# MCU.net
KiCad netlist of a schematic drawn in Altium Designer
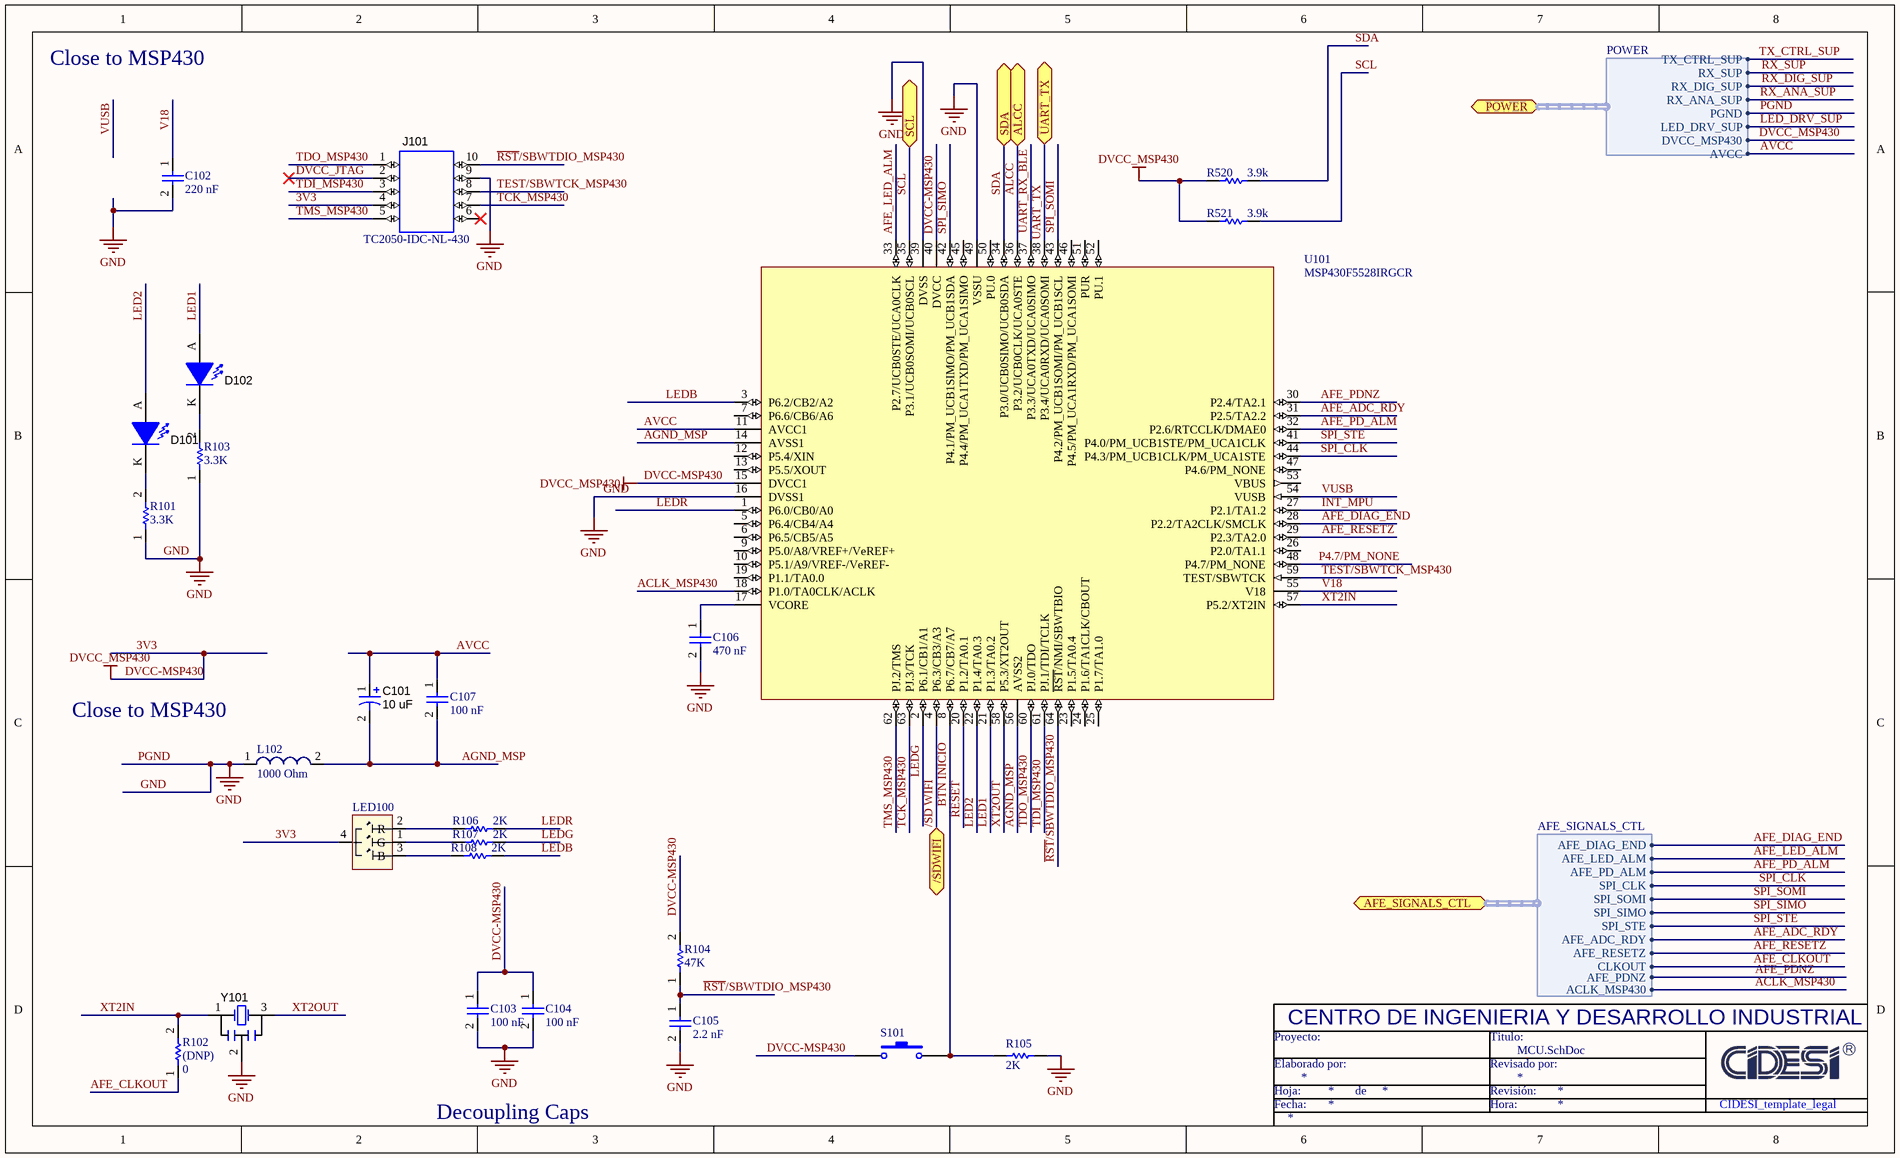
[diagram p0: MCU.SchDoc]

(export (version "E")
  (design (tool "Eeschema 10.0.6"))
  (components
    (comp (ref "C101")
      (value "10 uF")
      (footprint "C0603_P")
      (description "NICHICON - F981A106MMA - CAPACITOR TANT, 10UF, 10V 20%")
      (libsource (lib "TarjetaPrincipalV1_4") (part "F981A106MMA"))
    )
    (comp (ref "C102")
      (value "220 nF")
      (footprint "C0402")
      (description "TDK - C1005X7R1C224K050BC - CAP CERAMIC, 0.22UF, 16V, X7R, 0402")
      (libsource (lib "TarjetaPrincipalV1_4") (part "C1005X7R1C224K050BC"))
    )
    (comp (ref "C103")
      (value "100 nF")
      (footprint "C0402")
      (description "TDK - C1005X7R1H104M050BB - CAP CERAMIC, 0.1UF, 50V, X7R, 0402")
      (libsource (lib "TarjetaPrincipalV1_4") (part "C1005X7R1H104M050BB"))
    )
    (comp (ref "C104")
      (value "100 nF")
      (footprint "C0402")
      (description "TDK - C1005X7R1H104M050BB - CAP CERAMIC, 0.1UF, 50V, X7R, 0402")
      (libsource (lib "TarjetaPrincipalV1_4") (part "C1005X7R1H104M050BB"))
    )
    (comp (ref "C105")
      (value "2.2 nF")
      (footprint "C0402")
      (description "TDK - C1005X7R1H222K050BA - CAPACITOR CERAMIC 2200PF, 50V, X7R, 10%, 0402")
      (libsource (lib "5551-D_Wrist Watch") (part "C1005X7R1H222K050BA"))
    )
    (comp (ref "C106")
      (value "470 nF")
      (footprint "C0402")
      (description "TDK - C1005X5R1E474K050BB - CAP CERAMIC, 0.47UF, 25V, X5R, 0402")
      (libsource (lib "TarjetaPrincipalV1_4") (part "C1005X5R1E474K050BB"))
    )
    (comp (ref "C107")
      (value "100 nF")
      (footprint "C0402")
      (description "TDK - C1005X7R1H104M050BB - CAP CERAMIC, 0.1UF, 50V, X7R, 0402")
      (libsource (lib "TarjetaPrincipalV1_4") (part "C1005X7R1H104M050BB"))
    )
    (comp (ref "D101")
      (value "KPHHS-1005QBC-D-V")
      (footprint "LED_0402_BLUE")
      (description "KINGBRIGHT - KPHHS-1005QBC-D-V - LED, 0402, BLUE")
      (libsource (lib "TarjetaPrincipalV1_4") (part "LNJ947W8CRA"))
    )
    (comp (ref "D102")
      (value "2290341")
      (footprint "LED_0402_GREEN")
      (description "KINGBRIGHT - KPHHS-1005MGCK - LED, 0402, GREEN")
      (libsource (lib "TarjetaPrincipalV1_4") (part "APHHS1005CGCK"))
    )
    (comp (ref "J101")
      (value "TC2050-IDC-NL-430")
      (footprint "TC2050-IDC-NL")
      (description "CONNECTOR, PLUG OF NAILS CABLE, DUAL ROW, VERTICAL, 10-PIN")
      (fields (field (name "MANUFACTURER") "TAG CONNECT"))
      (libsource (lib "TarjetaPrincipalV1_4") (part "TC2050-IDC-NL-430"))
    )
    (comp (ref "L102")
      (value "1000 Ohm")
      (footprint "SMD 0402")
      (description "SMD EMI Suppression Ferrite Beads WE-CBF HF, Z= 1000 Ohm")
      (fields
        (field (name "PARTNO") "742841210")
        (field (name "MANUFACTURER") "Würth Elektronik eiSos GmbH")
        (field (name "CREATED BY") "Christin Zierenner")
      )
      (libsource (lib "TarjetaPrincipalV1_4") (part "WE-CBF HF 0402, 742841210"))
    )
    (comp (ref "LED100")
      (value "LED RGB AnodoComun")
      (footprint "LED-RGB 0606")
      (libsource (lib "TarjetaPrincipalV1_4") (part "LED RGB AnodoComun"))
    )
    (comp (ref "R101")
      (value "3.3K")
      (footprint "0201")
      (description "VISHAY DALE - CRCW02013K30FNED - RESISTOR, THICK FILM, 3.3 KOHM, 50 mW, 1%, FULL REEL")
      (libsource (lib "TarjetaPrincipalV1_4") (part "CRCW02013K30FNED"))
    )
    (comp (ref "R102")
      (value "(DNP)")
      (footprint "0201")
      (description "VISHAY DALE - CRCW02010000Z0ED - RESISTOR, CHIP, JUMPER, ZERO OHM, 50mW, FULL REEL")
      (fields (field (name "ALTIUM_VALUE") "0"))
      (libsource (lib "TarjetaPrincipalV1_4") (part "CRCW02010000Z0ED"))
    )
    (comp (ref "R103")
      (value "3.3K")
      (footprint "0201")
      (description "VISHAY DALE - CRCW02013K30FNED - RESISTOR, THICK FILM, 3.3 KOHM, 50 mW, 1%, FULL REEL")
      (libsource (lib "TarjetaPrincipalV1_4") (part "CRCW02013K30FNED"))
    )
    (comp (ref "R104")
      (value "47K")
      (footprint "0201")
      (description "VISHAY DALE - CRCW020147K0FNED - RESISTOR, THICK FILM, 47 KOHM, 50 mW, 1%, FULL REEL")
      (libsource (lib "TarjetaPrincipalV1_4") (part "CRCW020147K0FNED"))
    )
    (comp (ref "R105")
      (value "2K")
      (footprint "CR-0402")
      (description "Resistor")
      (fields (field (name "Comment") "Res1"))
      (libsource (lib "TarjetaPrincipalV1_4") (part "Res1"))
    )
    (comp (ref "R106")
      (value "2K")
      (footprint "CR-0402")
      (description "Resistor")
      (fields (field (name "Comment") "Res1"))
      (libsource (lib "TarjetaPrincipalV1_4") (part "Res1"))
    )
    (comp (ref "R107")
      (value "2K")
      (footprint "CR-0402")
      (description "Resistor")
      (fields (field (name "Comment") "Res1"))
      (libsource (lib "TarjetaPrincipalV1_4") (part "Res1"))
    )
    (comp (ref "R108")
      (value "2K")
      (footprint "CR-0402")
      (description "Resistor")
      (fields (field (name "Comment") "Res1"))
      (libsource (lib "TarjetaPrincipalV1_4") (part "Res1"))
    )
    (comp (ref "R520")
      (value "3.9k")
      (footprint "CR-0402")
      (description "Resistor")
      (fields (field (name "Comment") "Res 3.9K"))
      (libsource (lib "TarjetaPrincipalV1_4") (part "Res1_1"))
    )
    (comp (ref "R521")
      (value "3.9k")
      (footprint "CR-0402")
      (description "Resistor")
      (fields (field (name "Comment") "Res 3.9K"))
      (libsource (lib "TarjetaPrincipalV1_4") (part "Res1_1"))
    )
    (comp (ref "S101")
      (value "SW-PB")
      (footprint "TL3315")
      (description "Switch")
      (libsource (lib "TarjetaPrincipalV1_4") (part "SW-PB"))
    )
    (comp (ref "U101")
      (value "MSP430F5528IRGCR")
      (footprint "PVQFN-N64")
      (description "TEXAS INSTRUMENTS - MSP430F5528IRGCR - MCU, 16BIT, MSP430, 25MHZ, VQFN-64")
      (libsource (lib "TarjetaPrincipalV1_4") (part "MSP430F5528IRGC"))
    )
    (comp (ref "Y101")
      (value "CSTCR4M00G15L99-R0")
      (footprint "CRYSTAL-2X4.5MM_3P")
      (description "CRYSTAL, PIEZO CERAMIC RESONATOR, 4.00 MHz,  +/-0.1%, 39pF, SMD")
      (fields (field (name "MANUFACTURER") "MURATA") (field (name "TOLERANCE") "0.5 %"))
      (libsource (lib "TarjetaPrincipalV1_4") (part "CSTCR4M00G15L99-R0"))
    )
  )
  (nets
    (net (code "3") (name "/ACLK_MSP430") (class "Default")
      (node (ref "U101") (pin "18") (pinfunction "P1.0/TA0CLK/ACLK_18") (pintype "bidirectional"))
    )
    (net (code "4") (name "/AFE_ADC_RDY") (class "Default")
      (node (ref "U101") (pin "31") (pinfunction "P2.5/TA2.2_31") (pintype "bidirectional"))
    )
    (net (code "5") (name "/AFE_CLKOUT") (class "Default")
      (node (ref "R102") (pin "1") (pinfunction "1_1") (pintype "passive"))
    )
    (net (code "6") (name "/AFE_DIAG_END") (class "Default")
      (node (ref "U101") (pin "28") (pinfunction "P2.2/TA2CLK/SMCLK_28") (pintype "bidirectional"))
    )
    (net (code "7") (name "/AFE_LED_ALM") (class "Default")
      (node (ref "U101") (pin "33") (pinfunction "P2.7/UCB0STE/UCA0CLK_33") (pintype "bidirectional"))
    )
    (net (code "8") (name "/AFE_PDNZ") (class "Default")
      (node (ref "U101") (pin "30") (pinfunction "P2.4/TA2.1_30") (pintype "bidirectional"))
    )
    (net (code "9") (name "/AFE_PD_ALM") (class "Default")
      (node (ref "U101") (pin "32") (pinfunction "P2.6/RTCCLK/DMAE0_32") (pintype "bidirectional"))
    )
    (net (code "10") (name "/AFE_RESETZ") (class "Default")
      (node (ref "U101") (pin "29") (pinfunction "P2.3/TA2.0_29") (pintype "bidirectional"))
    )
    (net (code "11") (name "/AGND_MSP") (class "Default")
      (node (ref "C101") (pin "2") (pinfunction "-_2") (pintype "passive"))
      (node (ref "C107") (pin "2") (pinfunction "2_2") (pintype "passive"))
      (node (ref "L102") (pin "2") (pinfunction "2_2") (pintype "passive"))
      (node (ref "U101") (pin "14") (pinfunction "AVSS1_14") (pintype "power_in"))
      (node (ref "U101") (pin "56") (pinfunction "AVSS2_56") (pintype "power_in"))
    )
    (net (code "12") (name "/ALCC") (class "Default")
      (node (ref "U101") (pin "36") (pinfunction "P3.2/UCB0CLK/UCA0STE_36") (pintype "bidirectional"))
    )
    (net (code "13") (name "/AVCC") (class "Default")
      (node (ref "C101") (pin "1") (pinfunction "+_1") (pintype "passive"))
      (node (ref "C107") (pin "1") (pinfunction "1_1") (pintype "passive"))
      (node (ref "U101") (pin "11") (pinfunction "AVCC1_11") (pintype "power_in"))
    )
    (net (code "14") (name "/BTN INICIO") (class "Default")
      (node (ref "R105") (pin "2") (pinfunction "2_2") (pintype "passive"))
      (node (ref "S101") (pin "2") (pinfunction "2_2") (pintype "passive"))
      (node (ref "U101") (pin "8") (pinfunction "P6.7/CB7/A7_8") (pintype "bidirectional"))
    )
    (net (code "15") (name "/DVCC_JTAG") (class "Default")
      (node (ref "J101") (pin "2") (pinfunction "2_2") (pintype "bidirectional+no_connect"))
    )
    (net (code "16") (name "/INT_MPU") (class "Default")
      (node (ref "U101") (pin "27") (pinfunction "P2.1/TA1.2_27") (pintype "bidirectional"))
    )
    (net (code "17") (name "/LED1") (class "Default")
      (node (ref "D102") (pin "A") (pinfunction "A_A") (pintype "passive"))
      (node (ref "U101") (pin "21") (pinfunction "P1.3/TA0.2_21") (pintype "bidirectional"))
    )
    (net (code "18") (name "/LED2") (class "Default")
      (node (ref "D101") (pin "A") (pinfunction "A_A") (pintype "passive"))
      (node (ref "U101") (pin "22") (pinfunction "P1.4/TA0.3_22") (pintype "bidirectional"))
    )
    (net (code "19") (name "/LEDB") (class "Default")
      (node (ref "R108") (pin "1") (pinfunction "1_1") (pintype "passive"))
      (node (ref "U101") (pin "3") (pinfunction "P6.2/CB2/A2_3") (pintype "bidirectional"))
    )
    (net (code "20") (name "/LEDG") (class "Default")
      (node (ref "R107") (pin "1") (pinfunction "1_1") (pintype "passive"))
      (node (ref "U101") (pin "2") (pinfunction "P6.1/CB1/A1_2") (pintype "bidirectional"))
    )
    (net (code "21") (name "/LEDR") (class "Default")
      (node (ref "R106") (pin "1") (pinfunction "1_1") (pintype "passive"))
      (node (ref "U101") (pin "1") (pinfunction "P6.0/CB0/A0_1") (pintype "bidirectional"))
    )
    (net (code "23") (name "/P4.7{slash}PM_NONE") (class "Default")
      (node (ref "U101") (pin "48") (pinfunction "P4.7/PM_NONE_48") (pintype "bidirectional"))
    )
    (net (code "24") (name "/RESET") (class "Default")
      (node (ref "U101") (pin "20") (pinfunction "P1.2/TA0.1_20") (pintype "bidirectional"))
    )
    (net (code "28") (name "/SCL") (class "Default")
      (node (ref "R521") (pin "1") (pinfunction "1_1") (pintype "passive"))
      (node (ref "U101") (pin "35") (pinfunction "P3.1/UCB0SOMI/UCB0SCL_35") (pintype "bidirectional"))
    )
    (net (code "29") (name "/SDA") (class "Default")
      (node (ref "R520") (pin "1") (pinfunction "1_1") (pintype "passive"))
      (node (ref "U101") (pin "34") (pinfunction "P3.0/UCB0SIMO/UCB0SDA_34") (pintype "bidirectional"))
    )
    (net (code "30") (name "/SPI_CLK") (class "Default")
      (node (ref "U101") (pin "44") (pinfunction "P4.3/PM_UCB1CLK/PM_UCA1STE_44") (pintype "bidirectional"))
    )
    (net (code "31") (name "/SPI_SIMO") (class "Default")
      (node (ref "U101") (pin "42") (pinfunction "P4.1/PM_UCB1SIMO/PM_UCB1SDA_42") (pintype "bidirectional"))
    )
    (net (code "32") (name "/SPI_SOMI") (class "Default")
      (node (ref "U101") (pin "43") (pinfunction "P4.2/PM_UCB1SOMI/PM_UCB1SCL_43") (pintype "bidirectional"))
    )
    (net (code "33") (name "/SPI_STE") (class "Default")
      (node (ref "U101") (pin "41") (pinfunction "P4.0/PM_UCB1STE/PM_UCA1CLK_41") (pintype "bidirectional"))
    )
    (net (code "34") (name "/TCK_MSP430") (class "Default")
      (node (ref "J101") (pin "7") (pinfunction "7_7") (pintype "bidirectional"))
      (node (ref "U101") (pin "63") (pinfunction "PJ.3/TCK_63") (pintype "bidirectional"))
    )
    (net (code "35") (name "/TDI_MSP430") (class "Default")
      (node (ref "J101") (pin "3") (pinfunction "3_3") (pintype "bidirectional"))
      (node (ref "U101") (pin "61") (pinfunction "PJ.1/TDI/TCLK_61") (pintype "bidirectional"))
    )
    (net (code "36") (name "/TDO_MSP430") (class "Default")
      (node (ref "J101") (pin "1") (pinfunction "1_1") (pintype "bidirectional"))
      (node (ref "U101") (pin "60") (pinfunction "PJ.0/TDO_60") (pintype "bidirectional"))
    )
    (net (code "37") (name "/TEST{slash}SBWTCK_MSP430") (class "Default")
      (node (ref "J101") (pin "8") (pinfunction "8_8") (pintype "bidirectional"))
      (node (ref "U101") (pin "59") (pinfunction "TEST/SBWTCK_59") (pintype "input"))
    )
    (net (code "38") (name "/TMS_MSP430") (class "Default")
      (node (ref "J101") (pin "5") (pinfunction "5_5") (pintype "bidirectional"))
      (node (ref "U101") (pin "62") (pinfunction "PJ.2/TMS_62") (pintype "bidirectional"))
    )
    (net (code "40") (name "/UART_RX_BLE") (class "Default")
      (node (ref "U101") (pin "37") (pinfunction "P3.3/UCA0TXD/UCA0SIMO_37") (pintype "bidirectional"))
    )
    (net (code "41") (name "/UART_TX") (class "Default")
      (node (ref "U101") (pin "38") (pinfunction "P3.4/UCA0RXD/UCA0SOMI_38") (pintype "bidirectional"))
    )
    (net (code "42") (name "/V18") (class "Default")
      (node (ref "C102") (pin "1") (pinfunction "1_1") (pintype "passive"))
      (node (ref "U101") (pin "55") (pinfunction "V18_55") (pintype "power_in"))
    )
    (net (code "43") (name "/VUSB") (class "Default")
      (node (ref "U101") (pin "54") (pinfunction "VUSB_54") (pintype "input"))
    )
    (net (code "44") (name "/XT2IN") (class "Default")
      (node (ref "R102") (pin "2") (pinfunction "2_2") (pintype "passive"))
      (node (ref "U101") (pin "57") (pinfunction "P5.2/XT2IN_57") (pintype "bidirectional"))
      (node (ref "Y101") (pin "1") (pinfunction "1_1") (pintype "passive"))
    )
    (net (code "45") (name "/XT2OUT") (class "Default")
      (node (ref "U101") (pin "58") (pinfunction "P5.3/XT2OUT_58") (pintype "bidirectional"))
      (node (ref "Y101") (pin "3") (pinfunction "3_3") (pintype "passive"))
    )
    (net (code "48") (name "/{slash}SD WIFI") (class "Default")
      (node (ref "U101") (pin "4") (pinfunction "P6.3/CB3/A3_4") (pintype "bidirectional"))
    )
    (net (code "49") (name "/~{RST}{slash}SBWTDIO_MSP430") (class "Default")
      (node (ref "C105") (pin "1") (pinfunction "1_1") (pintype "passive"))
      (node (ref "J101") (pin "10") (pinfunction "10_10") (pintype "bidirectional"))
      (node (ref "R104") (pin "1") (pinfunction "1_1") (pintype "passive"))
      (node (ref "U101") (pin "64") (pinfunction "~{RST}/NMI/SBWTBIO_64") (pintype "bidirectional"))
    )
    (net (code "50") (name "DVCC_MSP430") (class "Default")
      (node (ref "C103") (pin "1") (pinfunction "1_1") (pintype "passive"))
      (node (ref "C104") (pin "1") (pinfunction "1_1") (pintype "passive"))
      (node (ref "J101") (pin "4") (pinfunction "4_4") (pintype "bidirectional"))
      (node (ref "LED100") (pin "4") (pintype "passive"))
      (node (ref "R104") (pin "2") (pinfunction "2_2") (pintype "passive"))
      (node (ref "R520") (pin "2") (pinfunction "2_2") (pintype "passive"))
      (node (ref "R521") (pin "2") (pinfunction "2_2") (pintype "passive"))
      (node (ref "S101") (pin "1") (pinfunction "1_1") (pintype "passive"))
      (node (ref "U101") (pin "15") (pinfunction "DVCC1_15") (pintype "power_in"))
      (node (ref "U101") (pin "40") (pinfunction "DVCC_40") (pintype "power_in"))
    )
    (net (code "51") (name "GND") (class "Default")
      (node (ref "C102") (pin "2") (pinfunction "2_2") (pintype "passive"))
      (node (ref "C103") (pin "2") (pinfunction "2_2") (pintype "passive"))
      (node (ref "C104") (pin "2") (pinfunction "2_2") (pintype "passive"))
      (node (ref "C105") (pin "2") (pinfunction "2_2") (pintype "passive"))
      (node (ref "C106") (pin "2") (pinfunction "2_2") (pintype "passive"))
      (node (ref "J101") (pin "9") (pinfunction "9_9") (pintype "bidirectional"))
      (node (ref "L102") (pin "1") (pinfunction "1_1") (pintype "passive"))
      (node (ref "R101") (pin "1") (pinfunction "1_1") (pintype "passive"))
      (node (ref "R103") (pin "1") (pinfunction "1_1") (pintype "passive"))
      (node (ref "R105") (pin "1") (pinfunction "1_1") (pintype "passive"))
      (node (ref "U101") (pin "16") (pinfunction "DVSS1_16") (pintype "power_in"))
      (node (ref "U101") (pin "39") (pinfunction "DVSS_39") (pintype "power_in"))
      (node (ref "U101") (pin "49") (pinfunction "VSSU_49") (pintype "power_in"))
      (node (ref "Y101") (pin "2") (pinfunction "2_2") (pintype "passive"))
    )
    (net (code "52") (name "Net-(D101-PadK)") (class "Default")
      (node (ref "D101") (pin "K") (pinfunction "K_K") (pintype "passive"))
      (node (ref "R101") (pin "2") (pinfunction "2_2") (pintype "passive"))
    )
    (net (code "53") (name "Net-(D102-PadK)") (class "Default")
      (node (ref "D102") (pin "K") (pinfunction "K_K") (pintype "passive"))
      (node (ref "R103") (pin "2") (pinfunction "2_2") (pintype "passive"))
    )
    (net (code "54") (name "Net-(LED100-B)") (class "Default")
      (node (ref "LED100") (pin "3") (pinfunction "B_3") (pintype "passive"))
      (node (ref "R108") (pin "2") (pinfunction "2_2") (pintype "passive"))
    )
    (net (code "55") (name "Net-(LED100-G)") (class "Default")
      (node (ref "LED100") (pin "1") (pinfunction "G_1") (pintype "passive"))
      (node (ref "R107") (pin "2") (pinfunction "2_2") (pintype "passive"))
    )
    (net (code "56") (name "Net-(LED100-R)") (class "Default")
      (node (ref "LED100") (pin "2") (pinfunction "R_2") (pintype "passive"))
      (node (ref "R106") (pin "2") (pinfunction "2_2") (pintype "passive"))
    )
    (net (code "57") (name "Net-(U101-VCORE)") (class "Default")
      (node (ref "C106") (pin "1") (pinfunction "1_1") (pintype "passive"))
      (node (ref "U101") (pin "17") (pinfunction "VCORE_17") (pintype "power_in"))
    )
    (net (code "58") (name "unconnected-(J101-Pad6)") (class "Default")
      (node (ref "J101") (pin "6") (pinfunction "6_6") (pintype "bidirectional+no_connect"))
    )
    (net (code "59") (name "unconnected-(U101-P1.1{slash}TA0.0-Pad19)") (class "Default")
      (node (ref "U101") (pin "19") (pinfunction "P1.1/TA0.0_19") (pintype "bidirectional"))
    )
    (net (code "60") (name "unconnected-(U101-P1.5{slash}TA0.4-Pad23)") (class "Default")
      (node (ref "U101") (pin "23") (pinfunction "P1.5/TA0.4_23") (pintype "bidirectional"))
    )
    (net (code "61") (name "unconnected-(U101-P1.6{slash}TA1CLK{slash}CBOUT-Pad24)") (class "Default")
      (node (ref "U101") (pin "24") (pinfunction "P1.6/TA1CLK/CBOUT_24") (pintype "bidirectional"))
    )
    (net (code "62") (name "unconnected-(U101-P1.7{slash}TA1.0-Pad25)") (class "Default")
      (node (ref "U101") (pin "25") (pinfunction "P1.7/TA1.0_25") (pintype "bidirectional"))
    )
    (net (code "63") (name "unconnected-(U101-P2.0{slash}TA1.1-Pad26)") (class "Default")
      (node (ref "U101") (pin "26") (pinfunction "P2.0/TA1.1_26") (pintype "bidirectional"))
    )
    (net (code "64") (name "unconnected-(U101-P4.4{slash}PM_UCA1TXD{slash}PM_UCA1SIMO-Pad45)") (class "Default")
      (node (ref "U101") (pin "45") (pinfunction "P4.4/PM_UCA1TXD/PM_UCA1SIMO_45") (pintype "bidirectional"))
    )
    (net (code "65") (name "unconnected-(U101-P4.5{slash}PM_UCA1RXD{slash}PM_UCA1SOMI-Pad46)") (class "Default")
      (node (ref "U101") (pin "46") (pinfunction "P4.5/PM_UCA1RXD/PM_UCA1SOMI_46") (pintype "bidirectional"))
    )
    (net (code "66") (name "unconnected-(U101-P4.6{slash}PM_NONE-Pad47)") (class "Default")
      (node (ref "U101") (pin "47") (pinfunction "P4.6/PM_NONE_47") (pintype "bidirectional"))
    )
    (net (code "67") (name "unconnected-(U101-P5.0{slash}A8{slash}VREF+{slash}VeREF+-Pad9)") (class "Default")
      (node (ref "U101") (pin "9") (pinfunction "P5.0/A8/VREF+/VeREF+_9") (pintype "bidirectional"))
    )
    (net (code "68") (name "unconnected-(U101-P5.1{slash}A9{slash}VREF-{slash}VeREF--Pad10)") (class "Default")
      (node (ref "U101") (pin "10") (pinfunction "P5.1/A9/VREF-/VeREF-_10") (pintype "bidirectional"))
    )
    (net (code "69") (name "unconnected-(U101-P5.4{slash}XIN-Pad12)") (class "Default")
      (node (ref "U101") (pin "12") (pinfunction "P5.4/XIN_12") (pintype "bidirectional"))
    )
    (net (code "70") (name "unconnected-(U101-P5.5{slash}XOUT-Pad13)") (class "Default")
      (node (ref "U101") (pin "13") (pinfunction "P5.5/XOUT_13") (pintype "bidirectional"))
    )
    (net (code "71") (name "unconnected-(U101-P6.4{slash}CB4{slash}A4-Pad5)") (class "Default")
      (node (ref "U101") (pin "5") (pinfunction "P6.4/CB4/A4_5") (pintype "bidirectional"))
    )
    (net (code "72") (name "unconnected-(U101-P6.5{slash}CB5{slash}A5-Pad6)") (class "Default")
      (node (ref "U101") (pin "6") (pinfunction "P6.5/CB5/A5_6") (pintype "bidirectional"))
    )
    (net (code "73") (name "unconnected-(U101-P6.6{slash}CB6{slash}A6-Pad7)") (class "Default")
      (node (ref "U101") (pin "7") (pinfunction "P6.6/CB6/A6_7") (pintype "bidirectional"))
    )
    (net (code "74") (name "unconnected-(U101-PU.0-Pad50)") (class "Default")
      (node (ref "U101") (pin "50") (pinfunction "PU.0_50") (pintype "bidirectional"))
    )
    (net (code "75") (name "unconnected-(U101-PU.1-Pad52)") (class "Default")
      (node (ref "U101") (pin "52") (pinfunction "PU.1_52") (pintype "bidirectional"))
    )
    (net (code "76") (name "unconnected-(U101-PUR-Pad51)") (class "Default")
      (node (ref "U101") (pin "51") (pinfunction "PUR_51") (pintype "bidirectional"))
    )
    (net (code "77") (name "unconnected-(U101-VBUS-Pad53)") (class "Default")
      (node (ref "U101") (pin "53") (pinfunction "VBUS_53") (pintype "output"))
    )
  )
)
